# sch_0034_121_pcb1_graphdone.net
KiCad netlist of a schematic drawn in EAGLE
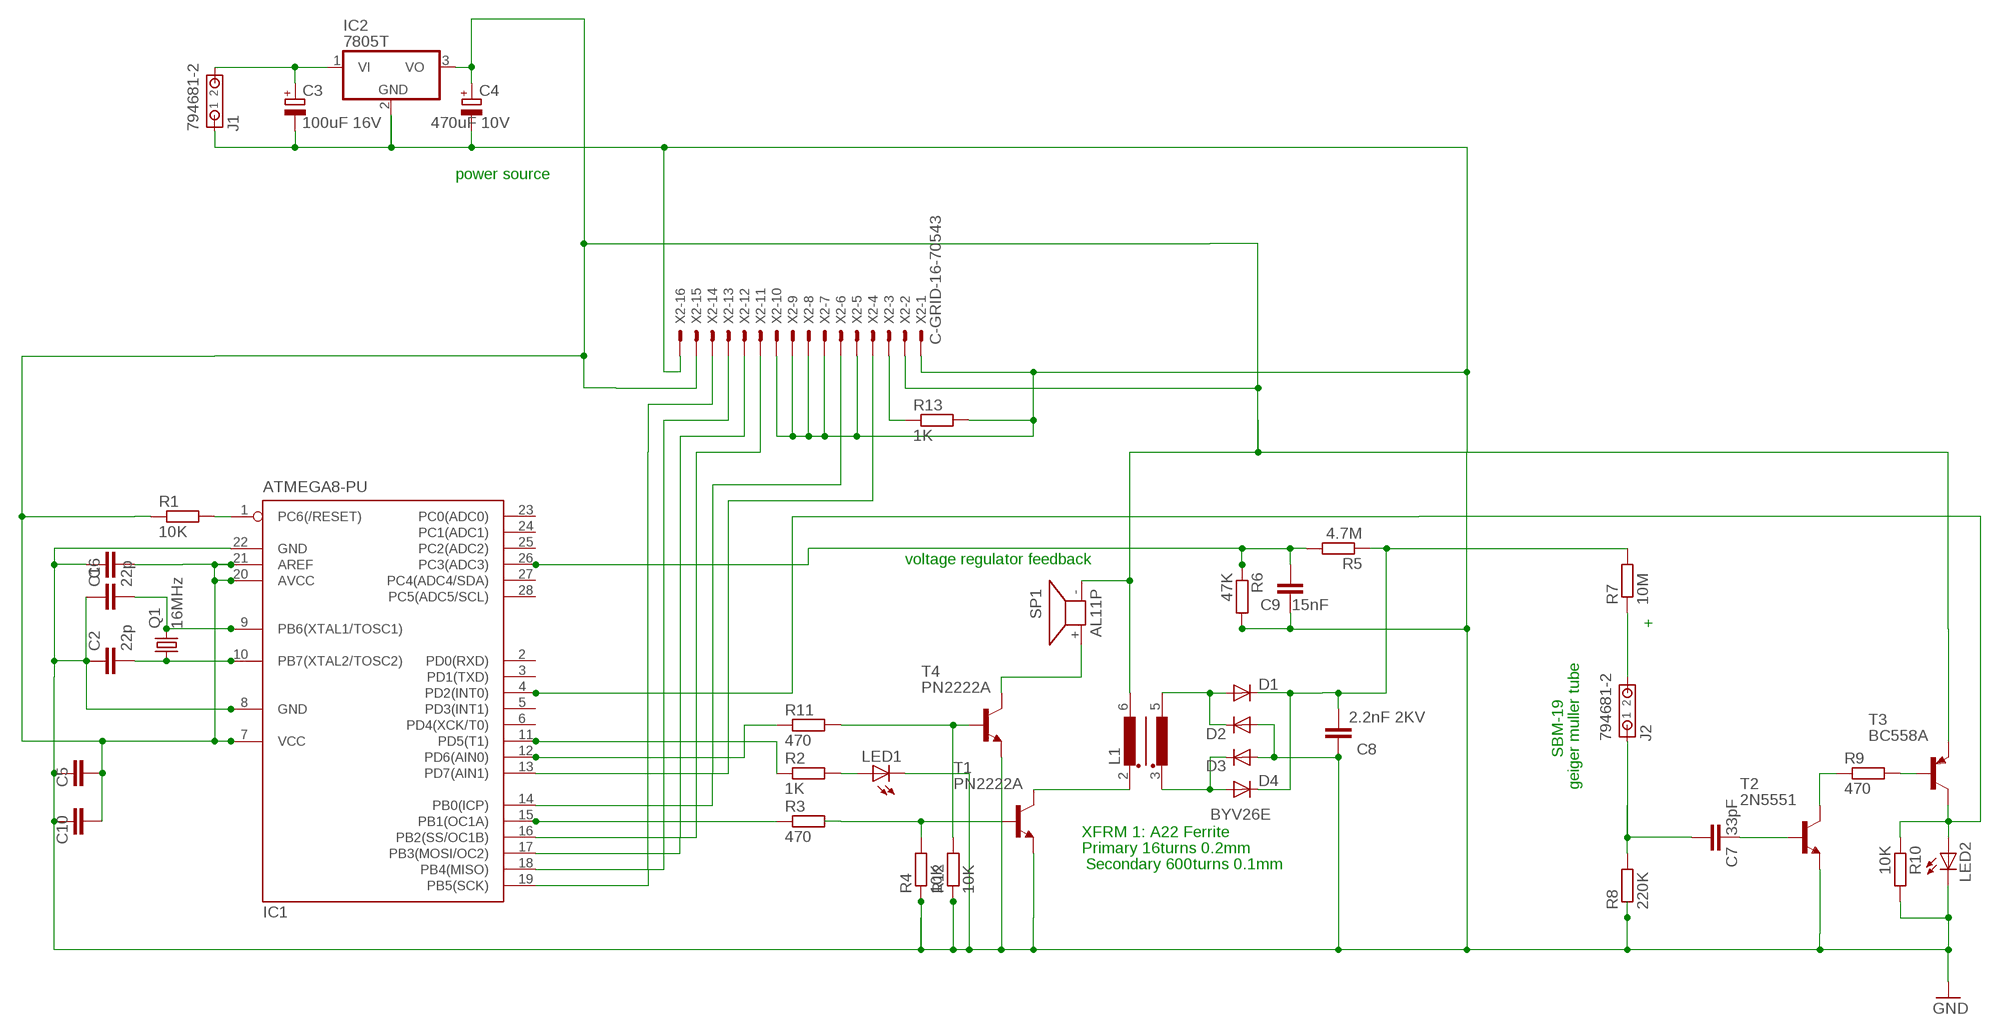
[diagram p0: schematic, sheet 1]

(export (version "E")
  (design (tool "Eeschema 10.0.6"))
  (components
    (comp (ref "C1")
      (value "22p")
      (footprint "eagle-import:C025-024X044")
      (libsource (lib "eagle-import") (part "C-EU025-024X044"))
    )
    (comp (ref "C2")
      (value "22p")
      (footprint "eagle-import:C025-024X044")
      (libsource (lib "eagle-import") (part "C-EU025-024X044"))
    )
    (comp (ref "C3")
      (value "100uF 16V")
      (footprint "eagle-import:E2,5-6E")
      (libsource (lib "eagle-import") (part "CPOL-EUE2,5-6E"))
    )
    (comp (ref "C4")
      (value "470uF 10V")
      (footprint "eagle-import:E2,5-6E")
      (libsource (lib "eagle-import") (part "CPOL-EUE2,5-6E"))
    )
    (comp (ref "C5")
      (value "100nF")
      (footprint "eagle-import:C025-024X044")
      (libsource (lib "eagle-import") (part "C-EU025-024X044"))
    )
    (comp (ref "C6")
      (value "100nF")
      (footprint "eagle-import:C025-024X044")
      (libsource (lib "eagle-import") (part "C-EU025-024X044"))
    )
    (comp (ref "C7")
      (value "33pF")
      (footprint "eagle-import:C025-024X044")
      (libsource (lib "eagle-import") (part "C-EU025-024X044"))
    )
    (comp (ref "C8")
      (value "2.2nF 2KV")
      (footprint "eagle-import:C025-024X044")
      (libsource (lib "eagle-import") (part "C-EU025-024X044"))
    )
    (comp (ref "C9")
      (value "15nF")
      (footprint "eagle-import:C025-024X044")
      (libsource (lib "eagle-import") (part "C-EU025-024X044"))
    )
    (comp (ref "C10")
      (value "100nF")
      (footprint "eagle-import:C025-024X044")
      (libsource (lib "eagle-import") (part "C-EU025-024X044"))
    )
    (comp (ref "D1")
      (value "DIODE-D-7.5")
      (footprint "eagle-import:D-7.5")
      (libsource (lib "eagle-import") (part "DIODE-D-7.5"))
    )
    (comp (ref "D2")
      (value "DIODE-D-7.5")
      (footprint "eagle-import:D-7.5")
      (libsource (lib "eagle-import") (part "DIODE-D-7.5"))
    )
    (comp (ref "D3")
      (value "DIODE-D-7.5")
      (footprint "eagle-import:D-7.5")
      (libsource (lib "eagle-import") (part "DIODE-D-7.5"))
    )
    (comp (ref "D4")
      (value "BYV26E")
      (footprint "eagle-import:D-7.5")
      (libsource (lib "eagle-import") (part "DIODE-D-7.5"))
    )
    (comp (ref "IC1")
      (value "ATMEGA8-PU")
      (footprint "eagle-import:DIL28-3")
      (libsource (lib "eagle-import") (part "MEGA8-P"))
    )
    (comp (ref "IC2")
      (value "7805T")
      (footprint "eagle-import:TO220H")
      (libsource (lib "eagle-import") (part "78T05"))
    )
    (comp (ref "J1")
      (value "794681-2")
      (footprint "eagle-import:794681-2")
      (libsource (lib "eagle-import") (part "794681-2"))
    )
    (comp (ref "J2")
      (value "794681-2")
      (footprint "eagle-import:794681-2")
      (libsource (lib "eagle-import") (part "794681-2"))
    )
    (comp (ref "L1")
      (value "RM6-2")
      (footprint "eagle-import:RM5-4")
      (libsource (lib "eagle-import") (part "RM6-2"))
    )
    (comp (ref "LED1")
      (value "LED3MM")
      (footprint "eagle-import:LED3MM")
      (libsource (lib "eagle-import") (part "LED3MM"))
    )
    (comp (ref "LED2")
      (value "LED3MM")
      (footprint "eagle-import:LED3MM")
      (libsource (lib "eagle-import") (part "LED3MM"))
    )
    (comp (ref "Q1")
      (value "16MHz")
      (footprint "eagle-import:HC49U-V")
      (libsource (lib "eagle-import") (part "CRYSTALHC49U-V"))
    )
    (comp (ref "R1")
      (value "10K")
      (footprint "eagle-import:0204_7")
      (libsource (lib "eagle-import") (part "R-EU_0204/7"))
    )
    (comp (ref "R2")
      (value "1K")
      (footprint "eagle-import:0204_7")
      (libsource (lib "eagle-import") (part "R-EU_0204/7"))
    )
    (comp (ref "R3")
      (value "470")
      (footprint "eagle-import:0204_7")
      (libsource (lib "eagle-import") (part "R-EU_0204/7"))
    )
    (comp (ref "R4")
      (value "10K")
      (footprint "eagle-import:0204_7")
      (libsource (lib "eagle-import") (part "R-EU_0204/7"))
    )
    (comp (ref "R5")
      (value "4.7M")
      (footprint "eagle-import:0204_7")
      (libsource (lib "eagle-import") (part "R-EU_0204/7"))
    )
    (comp (ref "R6")
      (value "47K")
      (footprint "eagle-import:0204_7")
      (libsource (lib "eagle-import") (part "R-EU_0204/7"))
    )
    (comp (ref "R7")
      (value "10M")
      (footprint "eagle-import:0204_7")
      (libsource (lib "eagle-import") (part "R-EU_0204/7"))
    )
    (comp (ref "R8")
      (value "220K")
      (footprint "eagle-import:0204_7")
      (libsource (lib "eagle-import") (part "R-EU_0204/7"))
    )
    (comp (ref "R9")
      (value "470")
      (footprint "eagle-import:0204_7")
      (libsource (lib "eagle-import") (part "R-EU_0204/7"))
    )
    (comp (ref "R10")
      (value "10K")
      (footprint "eagle-import:0204_7")
      (libsource (lib "eagle-import") (part "R-EU_0204/7"))
    )
    (comp (ref "R11")
      (value "470")
      (footprint "eagle-import:0204_7")
      (libsource (lib "eagle-import") (part "R-EU_0204/7"))
    )
    (comp (ref "R12")
      (value "10K")
      (footprint "eagle-import:0204_7")
      (libsource (lib "eagle-import") (part "R-EU_0204/7"))
    )
    (comp (ref "R13")
      (value "1K")
      (footprint "eagle-import:0204_7")
      (libsource (lib "eagle-import") (part "R-EU_0204/7"))
    )
    (comp (ref "SP1")
      (value "AL11P")
      (footprint "eagle-import:AL11P")
      (libsource (lib "eagle-import") (part "AL11P"))
    )
    (comp (ref "T1")
      (value "PN2222A")
      (footprint "eagle-import:TO92-EBC")
      (libsource (lib "eagle-import") (part "-NPN-TO92-EBC"))
    )
    (comp (ref "T2")
      (value "2N5551")
      (footprint "eagle-import:TO92-EBC")
      (libsource (lib "eagle-import") (part "-NPN-TO92-EBC"))
    )
    (comp (ref "T3")
      (value "BC558A")
      (footprint "eagle-import:TO92-EBC")
      (libsource (lib "eagle-import") (part "BC558A"))
    )
    (comp (ref "T4")
      (value "PN2222A")
      (footprint "eagle-import:TO92-EBC")
      (libsource (lib "eagle-import") (part "-NPN-TO92-EBC"))
    )
    (comp (ref "X2")
      (value "C-GRID-16-70543")
      (footprint "eagle-import:70543-16")
      (libsource (lib "eagle-import") (part "C-GRID-16-70543"))
    )
  )
  (nets
    (net (code "1") (name "GND") (class "Default")
      (node (ref "C1") (pin "1") (pinfunction "1_1") (pintype "passive"))
      (node (ref "C10") (pin "2") (pinfunction "2_2") (pintype "passive"))
      (node (ref "C2") (pin "1") (pinfunction "1_1") (pintype "passive"))
      (node (ref "C3") (pin "-") (pinfunction "-_-") (pintype "passive"))
      (node (ref "C4") (pin "-") (pinfunction "-_-") (pintype "passive"))
      (node (ref "C5") (pin "2") (pinfunction "2_2") (pintype "passive"))
      (node (ref "C6") (pin "2") (pinfunction "2_2") (pintype "passive"))
      (node (ref "C8") (pin "1") (pinfunction "1_1") (pintype "passive"))
      (node (ref "C9") (pin "1") (pinfunction "1_1") (pintype "passive"))
      (node (ref "D2") (pin "A") (pinfunction "A_A") (pintype "passive"))
      (node (ref "D3") (pin "A") (pinfunction "A_A") (pintype "passive"))
      (node (ref "IC1") (pin "22") (pinfunction "GND_22") (pintype "power_in"))
      (node (ref "IC1") (pin "8") (pinfunction "GND_8") (pintype "power_in"))
      (node (ref "IC2") (pin "2") (pinfunction "GND_2") (pintype "passive"))
      (node (ref "J1") (pin "1") (pinfunction "1_1") (pintype "passive"))
      (node (ref "LED1") (pin "K") (pinfunction "C_K") (pintype "passive"))
      (node (ref "LED2") (pin "K") (pinfunction "C_K") (pintype "passive"))
      (node (ref "R10") (pin "2") (pinfunction "2_2") (pintype "passive"))
      (node (ref "R12") (pin "1") (pinfunction "1_1") (pintype "passive"))
      (node (ref "R13") (pin "2") (pinfunction "2_2") (pintype "passive"))
      (node (ref "R4") (pin "1") (pinfunction "1_1") (pintype "passive"))
      (node (ref "R6") (pin "2") (pinfunction "2_2") (pintype "passive"))
      (node (ref "R8") (pin "1") (pinfunction "1_1") (pintype "passive"))
      (node (ref "T1") (pin "E") (pinfunction "E_E") (pintype "passive"))
      (node (ref "T2") (pin "E") (pinfunction "E_E") (pintype "passive"))
      (node (ref "T4") (pin "E") (pinfunction "E_E") (pintype "passive"))
      (node (ref "X2") (pin "1") (pinfunction "S_1") (pintype "passive"))
      (node (ref "X2") (pin "10") (pinfunction "S_10") (pintype "passive"))
      (node (ref "X2") (pin "16") (pinfunction "S_16") (pintype "passive"))
      (node (ref "X2") (pin "5") (pinfunction "S_5") (pintype "passive"))
      (node (ref "X2") (pin "7") (pinfunction "S_7") (pintype "passive"))
      (node (ref "X2") (pin "8") (pinfunction "S_8") (pintype "passive"))
      (node (ref "X2") (pin "9") (pinfunction "S_9") (pintype "passive"))
    )
    (net (code "2") (name "Net-(C7-Pad1)") (class "Default")
      (node (ref "C7") (pin "1") (pinfunction "1_1") (pintype "passive"))
      (node (ref "T2") (pin "B") (pinfunction "B_B") (pintype "passive"))
    )
    (net (code "3") (name "Net-(C7-Pad2)") (class "Default")
      (node (ref "C7") (pin "2") (pinfunction "2_2") (pintype "passive"))
      (node (ref "J2") (pin "1") (pinfunction "1_1") (pintype "passive"))
      (node (ref "R8") (pin "2") (pinfunction "2_2") (pintype "passive"))
    )
    (net (code "4") (name "Net-(C8-Pad2)") (class "Default")
      (node (ref "C8") (pin "2") (pinfunction "2_2") (pintype "passive"))
      (node (ref "D1") (pin "C") (pinfunction "C_C") (pintype "passive"))
      (node (ref "D4") (pin "C") (pinfunction "C_C") (pintype "passive"))
      (node (ref "R5") (pin "1") (pinfunction "1_1") (pintype "passive"))
      (node (ref "R7") (pin "2") (pinfunction "2_2") (pintype "passive"))
    )
    (net (code "5") (name "Net-(IC1-AREF)") (class "Default")
      (node (ref "C10") (pin "1") (pinfunction "1_1") (pintype "passive"))
      (node (ref "C4") (pin "+") (pinfunction "+_+") (pintype "passive"))
      (node (ref "C5") (pin "1") (pinfunction "1_1") (pintype "passive"))
      (node (ref "C6") (pin "1") (pinfunction "1_1") (pintype "passive"))
      (node (ref "IC1") (pin "20") (pinfunction "AVCC_20") (pintype "power_in"))
      (node (ref "IC1") (pin "21") (pinfunction "AREF_21") (pintype "passive"))
      (node (ref "IC1") (pin "7") (pinfunction "VCC_7") (pintype "power_in"))
      (node (ref "IC2") (pin "3") (pinfunction "VO_3") (pintype "passive"))
      (node (ref "L1") (pin "6") (pinfunction "W1E_6") (pintype "passive"))
      (node (ref "R1") (pin "1") (pinfunction "1_1") (pintype "passive"))
      (node (ref "SP1") (pin "-") (pinfunction "1_-") (pintype "passive"))
      (node (ref "T3") (pin "E") (pinfunction "E_E") (pintype "passive"))
      (node (ref "X2") (pin "15") (pinfunction "S_15") (pintype "passive"))
      (node (ref "X2") (pin "2") (pinfunction "S_2") (pintype "passive"))
    )
    (net (code "6") (name "Net-(IC1-PB0(ICP))") (class "Default")
      (node (ref "IC1") (pin "14") (pinfunction "PB0(ICP)_14") (pintype "bidirectional"))
      (node (ref "X2") (pin "6") (pinfunction "S_6") (pintype "passive"))
    )
    (net (code "7") (name "Net-(IC1-PB1(OC1A))") (class "Default")
      (node (ref "IC1") (pin "15") (pinfunction "PB1(OC1A)_15") (pintype "bidirectional"))
      (node (ref "R3") (pin "1") (pinfunction "1_1") (pintype "passive"))
    )
    (net (code "8") (name "Net-(IC1-PB2(SS{slash}OC1B))") (class "Default")
      (node (ref "IC1") (pin "16") (pinfunction "PB2(SS/OC1B)_16") (pintype "bidirectional"))
      (node (ref "X2") (pin "11") (pinfunction "S_11") (pintype "passive"))
    )
    (net (code "9") (name "Net-(IC1-PB3(MOSI{slash}OC2))") (class "Default")
      (node (ref "IC1") (pin "17") (pinfunction "PB3(MOSI/OC2)_17") (pintype "bidirectional"))
      (node (ref "X2") (pin "12") (pinfunction "S_12") (pintype "passive"))
    )
    (net (code "10") (name "Net-(IC1-PB4(MISO))") (class "Default")
      (node (ref "IC1") (pin "18") (pinfunction "PB4(MISO)_18") (pintype "bidirectional"))
      (node (ref "X2") (pin "13") (pinfunction "S_13") (pintype "passive"))
    )
    (net (code "11") (name "Net-(IC1-PB5(SCK))") (class "Default")
      (node (ref "IC1") (pin "19") (pinfunction "PB5(SCK)_19") (pintype "bidirectional"))
      (node (ref "X2") (pin "14") (pinfunction "S_14") (pintype "passive"))
    )
    (net (code "12") (name "Net-(IC1-PB6(XTAL1{slash}TOSC1))") (class "Default")
      (node (ref "C1") (pin "2") (pinfunction "2_2") (pintype "passive"))
      (node (ref "IC1") (pin "9") (pinfunction "PB6(XTAL1/TOSC1)_9") (pintype "bidirectional"))
      (node (ref "Q1") (pin "2") (pinfunction "2_2") (pintype "passive"))
    )
    (net (code "13") (name "Net-(IC1-PB7(XTAL2{slash}TOSC2))") (class "Default")
      (node (ref "C2") (pin "2") (pinfunction "2_2") (pintype "passive"))
      (node (ref "IC1") (pin "10") (pinfunction "PB7(XTAL2/TOSC2)_10") (pintype "bidirectional"))
      (node (ref "Q1") (pin "1") (pinfunction "1_1") (pintype "passive"))
    )
    (net (code "14") (name "Net-(IC1-PC3(ADC3))") (class "Default")
      (node (ref "C9") (pin "2") (pinfunction "2_2") (pintype "passive"))
      (node (ref "IC1") (pin "26") (pinfunction "PC3(ADC3)_26") (pintype "bidirectional"))
      (node (ref "R5") (pin "2") (pinfunction "2_2") (pintype "passive"))
      (node (ref "R6") (pin "1") (pinfunction "1_1") (pintype "passive"))
    )
    (net (code "15") (name "Net-(IC1-PC6({slash}RESET))") (class "Default")
      (node (ref "IC1") (pin "1") (pinfunction "PC6(/RESET)_1") (pintype "bidirectional"))
      (node (ref "R1") (pin "2") (pinfunction "2_2") (pintype "passive"))
    )
    (net (code "16") (name "Net-(IC1-PD2(INT0))") (class "Default")
      (node (ref "IC1") (pin "4") (pinfunction "PD2(INT0)_4") (pintype "bidirectional"))
      (node (ref "LED2") (pin "A") (pinfunction "A_A") (pintype "passive"))
      (node (ref "R10") (pin "1") (pinfunction "1_1") (pintype "passive"))
      (node (ref "T3") (pin "C") (pinfunction "C_C") (pintype "passive"))
    )
    (net (code "17") (name "Net-(IC1-PD5(T1))") (class "Default")
      (node (ref "IC1") (pin "11") (pinfunction "PD5(T1)_11") (pintype "bidirectional"))
      (node (ref "R2") (pin "1") (pinfunction "1_1") (pintype "passive"))
    )
    (net (code "18") (name "Net-(IC1-PD6(AIN0))") (class "Default")
      (node (ref "IC1") (pin "12") (pinfunction "PD6(AIN0)_12") (pintype "bidirectional"))
      (node (ref "R11") (pin "1") (pinfunction "1_1") (pintype "passive"))
    )
    (net (code "19") (name "Net-(IC1-PD7(AIN1))") (class "Default")
      (node (ref "IC1") (pin "13") (pinfunction "PD7(AIN1)_13") (pintype "bidirectional"))
      (node (ref "X2") (pin "4") (pinfunction "S_4") (pintype "passive"))
    )
    (net (code "20") (name "Net-(IC2-VI)") (class "Default")
      (node (ref "C3") (pin "+") (pinfunction "+_+") (pintype "passive"))
      (node (ref "IC2") (pin "1") (pinfunction "VI_1") (pintype "input"))
      (node (ref "J1") (pin "2") (pinfunction "2_2") (pintype "passive"))
    )
    (net (code "21") (name "Net-(J2-Pad2)") (class "Default")
      (node (ref "J2") (pin "2") (pinfunction "2_2") (pintype "passive"))
      (node (ref "R7") (pin "1") (pinfunction "1_1") (pintype "passive"))
    )
    (net (code "22") (name "Net-(L1-W1A)") (class "Default")
      (node (ref "L1") (pin "2") (pinfunction "W1A_2") (pintype "passive"))
      (node (ref "T1") (pin "C") (pinfunction "C_C") (pintype "passive"))
    )
    (net (code "23") (name "Net-(L1-W2A)") (class "Default")
      (node (ref "D3") (pin "C") (pinfunction "C_C") (pintype "passive"))
      (node (ref "D4") (pin "A") (pinfunction "A_A") (pintype "passive"))
      (node (ref "L1") (pin "3") (pinfunction "W2A_3") (pintype "passive"))
    )
    (net (code "24") (name "Net-(L1-W2E)") (class "Default")
      (node (ref "D1") (pin "A") (pinfunction "A_A") (pintype "passive"))
      (node (ref "D2") (pin "C") (pinfunction "C_C") (pintype "passive"))
      (node (ref "L1") (pin "5") (pinfunction "W2E_5") (pintype "passive"))
    )
    (net (code "25") (name "Net-(LED1-PadA)") (class "Default")
      (node (ref "LED1") (pin "A") (pinfunction "A_A") (pintype "passive"))
      (node (ref "R2") (pin "2") (pinfunction "2_2") (pintype "passive"))
    )
    (net (code "26") (name "Net-(R3-Pad2)") (class "Default")
      (node (ref "R3") (pin "2") (pinfunction "2_2") (pintype "passive"))
      (node (ref "R4") (pin "2") (pinfunction "2_2") (pintype "passive"))
      (node (ref "T1") (pin "B") (pinfunction "B_B") (pintype "passive"))
    )
    (net (code "27") (name "Net-(R9-Pad1)") (class "Default")
      (node (ref "R9") (pin "1") (pinfunction "1_1") (pintype "passive"))
      (node (ref "T2") (pin "C") (pinfunction "C_C") (pintype "passive"))
    )
    (net (code "28") (name "Net-(R9-Pad2)") (class "Default")
      (node (ref "R9") (pin "2") (pinfunction "2_2") (pintype "passive"))
      (node (ref "T3") (pin "B") (pinfunction "B_B") (pintype "passive"))
    )
    (net (code "29") (name "Net-(R11-Pad2)") (class "Default")
      (node (ref "R11") (pin "2") (pinfunction "2_2") (pintype "passive"))
      (node (ref "R12") (pin "2") (pinfunction "2_2") (pintype "passive"))
      (node (ref "T4") (pin "B") (pinfunction "B_B") (pintype "passive"))
    )
    (net (code "30") (name "Net-(SP1-2)") (class "Default")
      (node (ref "SP1") (pin "+") (pinfunction "2_+") (pintype "passive"))
      (node (ref "T4") (pin "C") (pinfunction "C_C") (pintype "passive"))
    )
    (net (code "31") (name "Net-(X2J-S)") (class "Default")
      (node (ref "R13") (pin "1") (pinfunction "1_1") (pintype "passive"))
      (node (ref "X2") (pin "3") (pinfunction "S_3") (pintype "passive"))
    )
    (net (code "32") (name "unconnected-(IC1-PC0(ADC0)-Pad23)") (class "Default")
      (node (ref "IC1") (pin "23") (pinfunction "PC0(ADC0)_23") (pintype "bidirectional"))
    )
    (net (code "33") (name "unconnected-(IC1-PC1(ADC1)-Pad24)") (class "Default")
      (node (ref "IC1") (pin "24") (pinfunction "PC1(ADC1)_24") (pintype "bidirectional"))
    )
    (net (code "34") (name "unconnected-(IC1-PC2(ADC2)-Pad25)") (class "Default")
      (node (ref "IC1") (pin "25") (pinfunction "PC2(ADC2)_25") (pintype "bidirectional"))
    )
    (net (code "35") (name "unconnected-(IC1-PC4(ADC4{slash}SDA)-Pad27)") (class "Default")
      (node (ref "IC1") (pin "27") (pinfunction "PC4(ADC4/SDA)_27") (pintype "bidirectional"))
    )
    (net (code "36") (name "unconnected-(IC1-PC5(ADC5{slash}SCL)-Pad28)") (class "Default")
      (node (ref "IC1") (pin "28") (pinfunction "PC5(ADC5/SCL)_28") (pintype "bidirectional"))
    )
    (net (code "37") (name "unconnected-(IC1-PD0(RXD)-Pad2)") (class "Default")
      (node (ref "IC1") (pin "2") (pinfunction "PD0(RXD)_2") (pintype "bidirectional"))
    )
    (net (code "38") (name "unconnected-(IC1-PD1(TXD)-Pad3)") (class "Default")
      (node (ref "IC1") (pin "3") (pinfunction "PD1(TXD)_3") (pintype "bidirectional"))
    )
    (net (code "39") (name "unconnected-(IC1-PD3(INT1)-Pad5)") (class "Default")
      (node (ref "IC1") (pin "5") (pinfunction "PD3(INT1)_5") (pintype "bidirectional"))
    )
    (net (code "40") (name "unconnected-(IC1-PD4(XCK{slash}T0)-Pad6)") (class "Default")
      (node (ref "IC1") (pin "6") (pinfunction "PD4(XCK/T0)_6") (pintype "bidirectional"))
    )
  )
)
